# Interface_21_04_33.net
KiCad netlist of a schematic drawn in Altium Designer
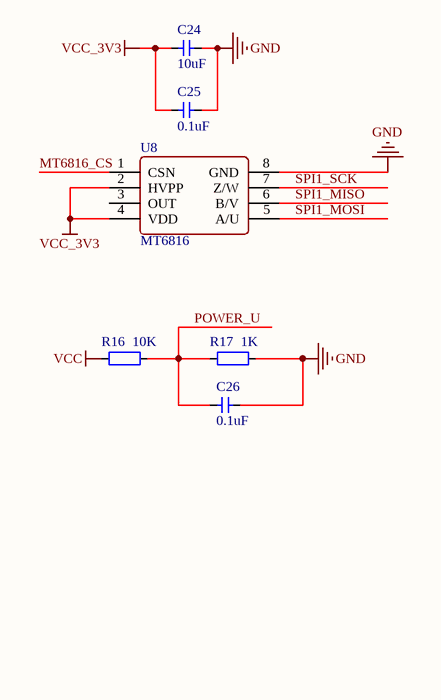
[diagram p0: Interface 21.04.33.SchDoc]

(export (version "E")
  (design (tool "Eeschema 10.0.6"))
  (components
    (comp (ref "C24")
      (value "10uF")
      (footprint "CAP_0402")
      (description "Capacitor")
      (libsource (lib "MyPcbLib") (part "电容-0402"))
    )
    (comp (ref "C25")
      (value "0.1uF")
      (footprint "motor42-lib:CAP_0402")
      (description "Capacitor")
      (libsource (lib "MyPcbLib") (part "电容-0402"))
    )
    (comp (ref "C26")
      (value "0.1uF")
      (footprint "motor42-lib:CAP_0402")
      (description "Capacitor")
      (libsource (lib "MyPcbLib") (part "电容-0402"))
    )
    (comp (ref "R16")
      (value "10K")
      (footprint "RES_0402")
      (description "Resistor")
      (libsource (lib "MyPcbLib") (part "电阻-0402"))
    )
    (comp (ref "R17")
      (value "1K")
      (footprint "RES_0402")
      (description "Resistor")
      (libsource (lib "MyPcbLib") (part "电阻-0402"))
    )
    (comp (ref "U8")
      (value "MT6816")
      (footprint "SO-8")
      (description "Magnetic Position Sensor")
      (libsource (lib "MyPcbLib") (part "MT6816"))
    )
  )
  (nets
    (net (code "1") (name "/MT6816_CS") (class "Default")
      (node (ref "U8") (pin "1") (pinfunction "CSN_1") (pintype "passive"))
    )
    (net (code "2") (name "/POWER_U") (class "Default")
      (node (ref "C26") (pin "2") (pinfunction "2_2") (pintype "passive"))
      (node (ref "R16") (pin "2") (pinfunction "2_2") (pintype "passive"))
      (node (ref "R17") (pin "1") (pinfunction "1_1") (pintype "passive"))
    )
    (net (code "3") (name "/SPI1_MISO") (class "Default")
      (node (ref "U8") (pin "6") (pinfunction "B/V_6") (pintype "passive"))
    )
    (net (code "4") (name "/SPI1_MOSI") (class "Default")
      (node (ref "U8") (pin "5") (pinfunction "A/U_5") (pintype "passive"))
    )
    (net (code "5") (name "/SPI1_SCK") (class "Default")
      (node (ref "U8") (pin "7") (pinfunction "Z/W_7") (pintype "passive"))
    )
    (net (code "6") (name "GND") (class "Default")
      (node (ref "C24") (pin "1") (pinfunction "1_1") (pintype "passive"))
      (node (ref "C25") (pin "1") (pinfunction "1_1") (pintype "passive"))
      (node (ref "C26") (pin "1") (pinfunction "1_1") (pintype "passive"))
      (node (ref "R17") (pin "2") (pinfunction "2_2") (pintype "passive"))
      (node (ref "U8") (pin "8") (pinfunction "GND_8") (pintype "passive"))
    )
    (net (code "7") (name "VCC") (class "Default")
      (node (ref "R16") (pin "1") (pinfunction "1_1") (pintype "passive"))
    )
    (net (code "8") (name "VCC_3V3") (class "Default")
      (node (ref "C24") (pin "2") (pinfunction "2_2") (pintype "passive"))
      (node (ref "C25") (pin "2") (pinfunction "2_2") (pintype "passive"))
      (node (ref "U8") (pin "2") (pinfunction "HVPP_2") (pintype "passive"))
      (node (ref "U8") (pin "4") (pinfunction "VDD_4") (pintype "passive"))
    )
    (net (code "9") (name "unconnected-(U8-OUT-Pad3)") (class "Default")
      (node (ref "U8") (pin "3") (pinfunction "OUT_3") (pintype "passive"))
    )
  )
)
